# sensors.net
KiCad netlist of a schematic drawn in Altium Designer
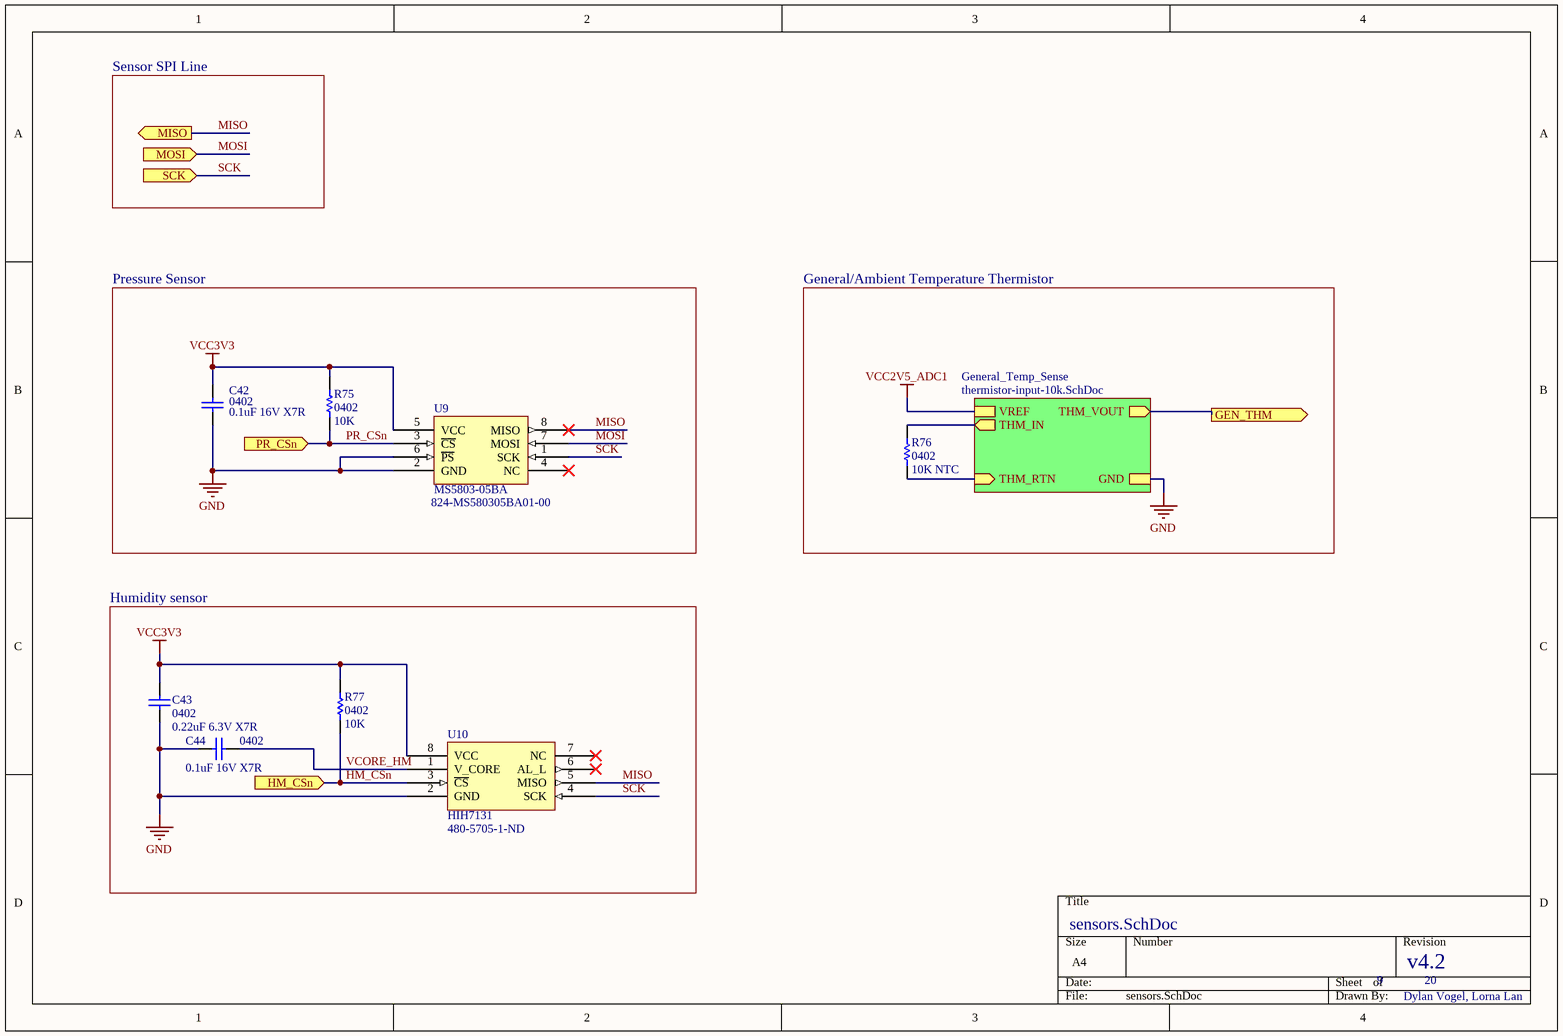
[diagram p0: sensors.SchDoc]

(export (version "E")
  (design (tool "Eeschema 10.0.6"))
  (components
    (comp (ref "C42")
      (value "0402")
      (footprint "CAP0402R")
      (description "0402 capacitor")
      (fields (field (name "ALTIUM_VALUE") "0.1uF 16V X7R"))
      (libsource (lib "heron-general") (part "CAP0402"))
    )
    (comp (ref "C43")
      (value "0402")
      (footprint "CAP0402R")
      (description "0402 capacitor")
      (fields (field (name "ALTIUM_VALUE") "0.22uF 6.3V X7R"))
      (libsource (lib "CAP0402") (part "CAP0402"))
    )
    (comp (ref "C44")
      (value "0402")
      (footprint "CAP0402R")
      (description "0402 capacitor")
      (fields (field (name "ALTIUM_VALUE") "0.1uF 16V X7R"))
      (libsource (lib "heron-general") (part "CAP0402"))
    )
    (comp (ref "R75")
      (value "0402")
      (footprint "RES0402R")
      (description "0402 resistor")
      (fields
        (field (name "ALTIUM_VALUE") "10K")
        (field (name "MANUFACTURER") "Panasonic")
        (field (name "MANUFACTURER PART NUMBER") "ERJ-2RKF1002X")
      )
      (libsource (lib "heron-general") (part "RES0402"))
    )
    (comp (ref "R76")
      (value "0402")
      (footprint "RES0402R")
      (description "0402 resistor")
      (fields (field (name "ALTIUM_VALUE") "10K NTC"))
      (libsource (lib "heron-general") (part "RES0402"))
    )
    (comp (ref "R77")
      (value "0402")
      (footprint "RES0402R")
      (description "0402 resistor")
      (fields
        (field (name "ALTIUM_VALUE") "10K")
        (field (name "MANUFACTURER") "Panasonic")
        (field (name "MANUFACTURER PART NUMBER") "ERJ-2RKF1002X")
      )
      (libsource (lib "heron-general") (part "RES0402"))
    )
    (comp (ref "U9")
      (value "MS5803-05BA")
      (footprint "MS5803_125P640x620-8N")
      (fields (field (name "SUPPLIER PART NUMBER 1") "824-MS580305BA01-00"))
      (libsource (lib "PAY") (part "MS5803-05BA"))
    )
    (comp (ref "U10")
      (value "HIH7131")
      (footprint "SOIC127P500X600-8N")
      (fields (field (name "SUPPLIER PART NUMBER 1") "480-5705-1-ND"))
      (libsource (lib "PAY") (part "HIH7131"))
    )
  )
  (nets
    (net (code "2") (name "/HM_CSn") (class "Default")
      (node (ref "R77") (pin "1") (pinfunction "1_1") (pintype "passive"))
      (node (ref "U10") (pin "3") (pinfunction "~{CS}_3") (pintype "input"))
    )
    (net (code "3") (name "/MISO") (class "Default")
      (node (ref "U10") (pin "5") (pinfunction "MISO_5") (pintype "output"))
      (node (ref "U9") (pin "8") (pinfunction "MISO_8") (pintype "output"))
    )
    (net (code "4") (name "/MOSI") (class "Default")
      (node (ref "U9") (pin "7") (pinfunction "MOSI_7") (pintype "input"))
    )
    (net (code "5") (name "/PR_CSn") (class "Default")
      (node (ref "R75") (pin "1") (pinfunction "1_1") (pintype "passive"))
      (node (ref "U9") (pin "3") (pinfunction "~{CS}_3") (pintype "input"))
    )
    (net (code "6") (name "/SCK") (class "Default")
      (node (ref "U10") (pin "4") (pinfunction "SCK_4") (pintype "input"))
      (node (ref "U9") (pin "1") (pinfunction "SCK_1") (pintype "input"))
    )
    (net (code "7") (name "/THM_IN") (class "Default")
      (node (ref "R76") (pin "2") (pinfunction "2_2") (pintype "passive"))
    )
    (net (code "8") (name "/THM_RTN") (class "Default")
      (node (ref "R76") (pin "1") (pinfunction "1_1") (pintype "passive"))
    )
    (net (code "9") (name "/VCORE_HM") (class "Default")
      (node (ref "C44") (pin "2") (pinfunction "2_2") (pintype "passive"))
      (node (ref "U10") (pin "1") (pinfunction "V_CORE_1") (pintype "power_in"))
    )
    (net (code "10") (name "GND") (class "Default")
      (node (ref "C42") (pin "1") (pinfunction "1_1") (pintype "passive"))
      (node (ref "C43") (pin "1") (pinfunction "1_1") (pintype "passive"))
      (node (ref "C44") (pin "1") (pinfunction "1_1") (pintype "passive"))
      (node (ref "U10") (pin "2") (pinfunction "GND_2") (pintype "power_in"))
      (node (ref "U9") (pin "2") (pinfunction "GND_2") (pintype "power_in"))
      (node (ref "U9") (pin "6") (pinfunction "~{PS}_6") (pintype "input"))
    )
    (net (code "12") (name "VCC3V3") (class "Default")
      (node (ref "C42") (pin "2") (pinfunction "2_2") (pintype "passive"))
      (node (ref "C43") (pin "2") (pinfunction "2_2") (pintype "passive"))
      (node (ref "R75") (pin "2") (pinfunction "2_2") (pintype "passive"))
      (node (ref "R77") (pin "2") (pinfunction "2_2") (pintype "passive"))
      (node (ref "U10") (pin "8") (pinfunction "VCC_8") (pintype "power_in"))
      (node (ref "U9") (pin "5") (pinfunction "VCC_5") (pintype "power_in"))
    )
    (net (code "13") (name "unconnected-(U9-NC-Pad4)") (class "Default")
      (node (ref "U9") (pin "4") (pinfunction "NC_4") (pintype "passive+no_connect"))
    )
    (net (code "14") (name "unconnected-(U10-AL_L-Pad6)") (class "Default")
      (node (ref "U10") (pin "6") (pinfunction "AL_L_6") (pintype "output+no_connect"))
    )
    (net (code "15") (name "unconnected-(U10-NC-Pad7)") (class "Default")
      (node (ref "U10") (pin "7") (pinfunction "NC_7") (pintype "passive+no_connect"))
    )
  )
)
